# 13_Periphs.net
KiCad netlist of a schematic drawn in Altium Designer
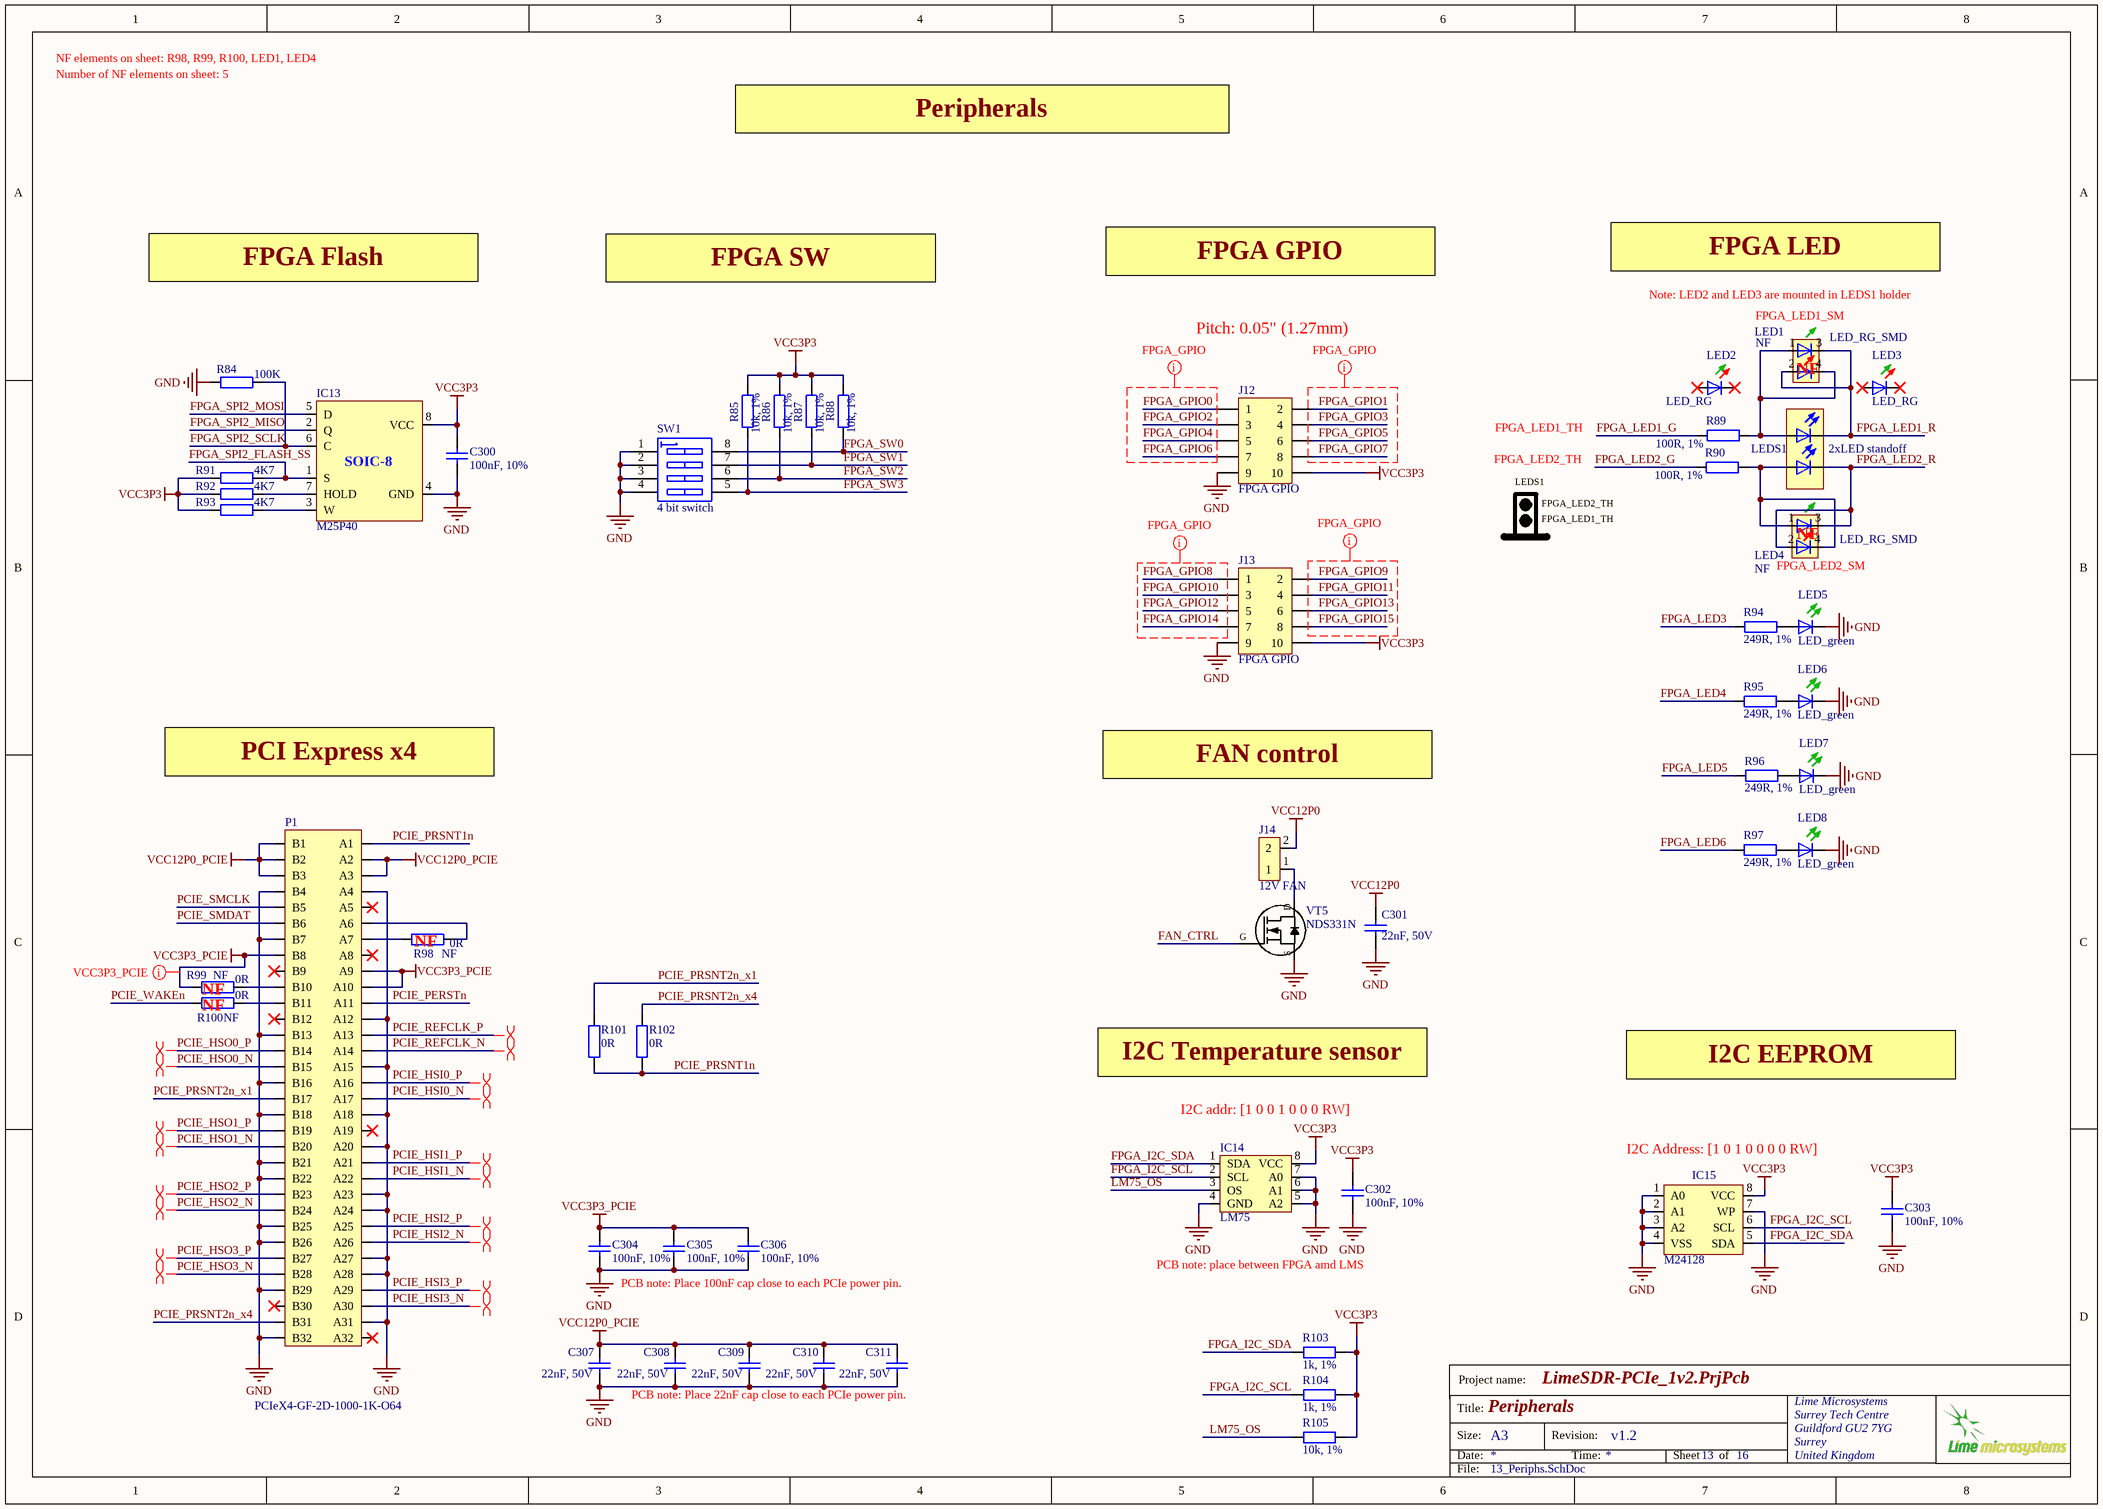
[diagram p0: 13_Periphs.SchDoc]

(export (version "E")
  (design (tool "Eeschema 10.0.6"))
  (components
    (comp (ref "C300")
      (value "100nF, 10%")
      (footprint "CAP0402")
      (fields
        (field (name "TOLERANCE") "10 %")
        (field (name "MANUFACTURER") "Murata Electronics")
        (field (name "MANUFACTURER PART NUMBER") "GRM155R71C104KA88D")
      )
      (libsource (lib "LimeFPGAboard_schLib") (part "Cap_0603"))
    )
    (comp (ref "C301")
      (value "22nF, 50V")
      (footprint "CAP0402")
      (fields (field (name "TOLERANCE") "±10%") (field (name "MANUFACTURER") "Kemet"))
      (libsource (lib "LimeMicroAltiumLib_schLib") (part "Cap_0402"))
    )
    (comp (ref "C302")
      (value "100nF, 10%")
      (footprint "CAP0402")
      (fields
        (field (name "TOLERANCE") "10 %")
        (field (name "MANUFACTURER") "Murata Electronics")
        (field (name "MANUFACTURER PART NUMBER") "GRM155R71C104KA88D")
      )
      (libsource (lib "LimeFPGAboard_schLib") (part "Cap_0603"))
    )
    (comp (ref "C303")
      (value "100nF, 10%")
      (footprint "CAP0402")
      (fields
        (field (name "TOLERANCE") "10 %")
        (field (name "MANUFACTURER") "Murata Electronics")
        (field (name "MANUFACTURER PART NUMBER") "GRM155R71C104KA88D")
      )
      (libsource (lib "LimeFPGAboard_schLib") (part "Cap_0603"))
    )
    (comp (ref "C304")
      (value "100nF, 10%")
      (footprint "CAP0402")
      (fields
        (field (name "TOLERANCE") "10 %")
        (field (name "MANUFACTURER") "Murata Electronics")
        (field (name "MANUFACTURER PART NUMBER") "GRM155R71C104KA88D")
      )
      (libsource (lib "LimeFPGAboard_schLib") (part "Cap_0603"))
    )
    (comp (ref "C305")
      (value "100nF, 10%")
      (footprint "CAP0402")
      (fields
        (field (name "TOLERANCE") "10 %")
        (field (name "MANUFACTURER") "Murata Electronics")
        (field (name "MANUFACTURER PART NUMBER") "GRM155R71C104KA88D")
      )
      (libsource (lib "LimeFPGAboard_schLib") (part "Cap_0603"))
    )
    (comp (ref "C306")
      (value "100nF, 10%")
      (footprint "CAP0402")
      (fields
        (field (name "TOLERANCE") "10 %")
        (field (name "MANUFACTURER") "Murata Electronics")
        (field (name "MANUFACTURER PART NUMBER") "GRM155R71C104KA88D")
      )
      (libsource (lib "LimeFPGAboard_schLib") (part "Cap_0603"))
    )
    (comp (ref "C307")
      (value "22nF, 50V")
      (footprint "CAP0402")
      (fields (field (name "TOLERANCE") "±10%") (field (name "MANUFACTURER") "Kemet"))
      (libsource (lib "LimeMicroAltiumLib_schLib") (part "Cap_0402"))
    )
    (comp (ref "C308")
      (value "22nF, 50V")
      (footprint "CAP0402")
      (fields (field (name "TOLERANCE") "±10%") (field (name "MANUFACTURER") "Kemet"))
      (libsource (lib "LimeMicroAltiumLib_schLib") (part "Cap_0402"))
    )
    (comp (ref "C309")
      (value "22nF, 50V")
      (footprint "CAP0402")
      (fields (field (name "TOLERANCE") "±10%") (field (name "MANUFACTURER") "Kemet"))
      (libsource (lib "LimeMicroAltiumLib_schLib") (part "Cap_0402"))
    )
    (comp (ref "C310")
      (value "22nF, 50V")
      (footprint "CAP0402")
      (fields (field (name "TOLERANCE") "±10%") (field (name "MANUFACTURER") "Kemet"))
      (libsource (lib "LimeMicroAltiumLib_schLib") (part "Cap_0402"))
    )
    (comp (ref "C311")
      (value "22nF, 50V")
      (footprint "CAP0402")
      (fields (field (name "TOLERANCE") "±10%") (field (name "MANUFACTURER") "Kemet"))
      (libsource (lib "LimeMicroAltiumLib_schLib") (part "Cap_0402"))
    )
    (comp (ref "IC13")
      (value "M25P40")
      (footprint "M25P40-VMN6TPB_SO8N")
      (fields (field (name "MANUFACTURER") "Micron Technology Inc"))
      (libsource (lib "LimeFPGAboard_schLib") (part "M25P40"))
    )
    (comp (ref "IC14")
      (value "LM75")
      (footprint "HWSON8_LM75")
      (fields
        (field (name "MANUFACTURER") "NXP Semiconductors")
        (field (name "MANUFACTURER PART NUMBER") "LM75BTP,147")
      )
      (libsource (lib "LimeMicroAltiumLib_schLib") (part "LM75"))
    )
    (comp (ref "IC15")
      (value "M24128")
      (footprint "24FC512")
      (fields (field (name "MANUFACTURER") "STMicroelectronics"))
      (libsource (lib "LimeMicroAltiumLib_schLib") (part "24FC64F"))
    )
    (comp (ref "J12")
      (value "FPGA GPIO")
      (footprint "SWD_10_pin")
      (description "Header, 5-Pin, Dual row")
      (fields (field (name "MANUFACTURER") "Harwin Inc"))
      (libsource (lib "LimeMicroAltiumLib_schLib") (part "Header 5X2_SWD"))
    )
    (comp (ref "J13")
      (value "FPGA GPIO")
      (footprint "SWD_10_pin")
      (description "Header, 5-Pin, Dual row")
      (fields (field (name "MANUFACTURER") "Harwin Inc"))
      (libsource (lib "LimeMicroAltiumLib_schLib") (part "Header 5X2_SWD"))
    )
    (comp (ref "J14")
      (value "12V FAN")
      (footprint "HDR_1x2")
      (fields (field (name "MANUFACTURER") "3M"))
      (libsource (lib "LimeFPGAboard_schLib") (part "Jumper"))
    )
    (comp (ref "LED1")
      (value "LED_RG_SMD")
      (footprint "LED-2x0603")
      (fields (field (name "MANUFACTURER") "Avago Technologies US Inc.") (field (name "ASSEMBLY INFO") "NF"))
      (libsource (lib "LimeMicroAltiumLib_schLib") (part "LED_green_red_SMD"))
    )
    (comp (ref "LED2")
      (value "LED_RG")
      (fields (field (name "MANUFACTURER") "Visual Communications Company - VCC"))
      (libsource (lib "LimeMicroAltiumLib_schLib") (part "LED_green_red"))
    )
    (comp (ref "LED3")
      (value "LED_RG")
      (fields (field (name "MANUFACTURER") "Visual Communications Company - VCC"))
      (libsource (lib "LimeMicroAltiumLib_schLib") (part "LED_green_red"))
    )
    (comp (ref "LED4")
      (value "LED_RG_SMD")
      (footprint "LED-2x0603")
      (fields (field (name "MANUFACTURER") "Avago Technologies US Inc.") (field (name "ASSEMBLY INFO") "NF"))
      (libsource (lib "LimeMicroAltiumLib_schLib") (part "LED_green_red_SMD"))
    )
    (comp (ref "LED5")
      (value "LED_green")
      (footprint "LED-0603-GREEN")
      (fields (field (name "MANUFACTURER") "Broadcom Limited"))
      (libsource (lib "LimeFPGAboard_schLib") (part "LED_green"))
    )
    (comp (ref "LED6")
      (value "LED_green")
      (footprint "LED-0603-GREEN")
      (fields (field (name "MANUFACTURER") "Broadcom Limited"))
      (libsource (lib "LimeFPGAboard_schLib") (part "LED_green"))
    )
    (comp (ref "LED7")
      (value "LED_green")
      (footprint "LED-0603-GREEN")
      (fields (field (name "MANUFACTURER") "Broadcom Limited"))
      (libsource (lib "LimeFPGAboard_schLib") (part "LED_green"))
    )
    (comp (ref "LED8")
      (value "LED_green")
      (footprint "LED-0603-GREEN")
      (fields (field (name "MANUFACTURER") "Broadcom Limited"))
      (libsource (lib "LimeFPGAboard_schLib") (part "LED_green"))
    )
    (comp (ref "LEDS1")
      (value "2xLED standoff")
      (footprint "LED_STANDOFF_H-201C")
      (fields (field (name "MANUFACTURER") "Bivar Inc."))
      (libsource (lib "LimeMicroAltiumLib_schLib") (part "LEDx2_STANDOFF"))
    )
    (comp (ref "P1")
      (value "PCIeX4-GF-2D-1000-1K-O64")
      (footprint "PCIeX4-GF-2D-1000-1K-O64")
      (libsource (lib "LimeMicroAltiumLib_schLib") (part "PCIeX4-GF-2D-1000-1K-O64"))
    )
    (comp (ref "R84")
      (value "100K")
      (footprint "RES0402")
      (fields
        (field (name "TOLERANCE") "±5%")
        (field (name "MANUFACTURER") "Panasonic Electronic Components")
      )
      (libsource (lib "LimeFPGAboard_schLib") (part "Res_0402"))
    )
    (comp (ref "R85")
      (value "10k, 1%")
      (footprint "RES0402")
      (fields (field (name "MANUFACTURER") "Yageo") (field (name "TOLERANCE") "±1%"))
      (libsource (lib "LimeMicroAltiumLib_schLib") (part "Res_0402"))
    )
    (comp (ref "R86")
      (value "10k, 1%")
      (footprint "RES0402")
      (fields (field (name "MANUFACTURER") "Yageo") (field (name "TOLERANCE") "±1%"))
      (libsource (lib "LimeMicroAltiumLib_schLib") (part "Res_0402"))
    )
    (comp (ref "R87")
      (value "10k, 1%")
      (footprint "RES0402")
      (fields (field (name "MANUFACTURER") "Yageo") (field (name "TOLERANCE") "±1%"))
      (libsource (lib "LimeMicroAltiumLib_schLib") (part "Res_0402"))
    )
    (comp (ref "R88")
      (value "10k, 1%")
      (footprint "RES0402")
      (fields (field (name "MANUFACTURER") "Yageo") (field (name "TOLERANCE") "±1%"))
      (libsource (lib "LimeMicroAltiumLib_schLib") (part "Res_0402"))
    )
    (comp (ref "R89")
      (value "100R, 1%")
      (footprint "RES0402")
      (fields (field (name "TOLERANCE") "±1%") (field (name "MANUFACTURER") "Stackpole Electronics Inc."))
      (libsource (lib "LimeMicroAltiumLib_schLib") (part "Res_0402"))
    )
    (comp (ref "R90")
      (value "100R, 1%")
      (footprint "RES0402")
      (fields (field (name "TOLERANCE") "±1%") (field (name "MANUFACTURER") "Stackpole Electronics Inc."))
      (libsource (lib "LimeMicroAltiumLib_schLib") (part "Res_0402"))
    )
    (comp (ref "R91")
      (value "4K7")
      (footprint "RES0402")
      (fields (field (name "TOLERANCE") "±5%") (field (name "MANUFACTURER") "Stackpole Electronics Inc."))
      (libsource (lib "LimeFPGAboard_schLib") (part "Res_0402"))
    )
    (comp (ref "R92")
      (value "4K7")
      (footprint "RES0402")
      (fields (field (name "TOLERANCE") "±5%") (field (name "MANUFACTURER") "Stackpole Electronics Inc."))
      (libsource (lib "LimeFPGAboard_schLib") (part "Res_0402"))
    )
    (comp (ref "R93")
      (value "4K7")
      (footprint "RES0402")
      (fields (field (name "TOLERANCE") "±5%") (field (name "MANUFACTURER") "Stackpole Electronics Inc."))
      (libsource (lib "LimeFPGAboard_schLib") (part "Res_0402"))
    )
    (comp (ref "R94")
      (value "249R, 1%")
      (footprint "RES0402")
      (fields (field (name "MANUFACTURER") "Stackpole Electronics Inc") (field (name "TOLERANCE") "±1%"))
      (libsource (lib "LimeMicroAltiumLib_schLib") (part "Res_0402"))
    )
    (comp (ref "R95")
      (value "249R, 1%")
      (footprint "RES0402")
      (fields (field (name "MANUFACTURER") "Stackpole Electronics Inc") (field (name "TOLERANCE") "±1%"))
      (libsource (lib "LimeMicroAltiumLib_schLib") (part "Res_0402"))
    )
    (comp (ref "R96")
      (value "249R, 1%")
      (footprint "RES0402")
      (fields (field (name "MANUFACTURER") "Stackpole Electronics Inc") (field (name "TOLERANCE") "±1%"))
      (libsource (lib "LimeMicroAltiumLib_schLib") (part "Res_0402"))
    )
    (comp (ref "R97")
      (value "249R, 1%")
      (footprint "RES0402")
      (fields (field (name "MANUFACTURER") "Stackpole Electronics Inc") (field (name "TOLERANCE") "±1%"))
      (libsource (lib "LimeMicroAltiumLib_schLib") (part "Res_0402"))
    )
    (comp (ref "R98")
      (value "0R")
      (footprint "RES0402")
      (fields (field (name "MANUFACTURER") "Yageo") (field (name "ASSEMBLY INFO") "NF"))
      (libsource (lib "LimeFPGAboard_schLib") (part "Res_0402"))
    )
    (comp (ref "R99")
      (value "0R")
      (footprint "RES0402")
      (fields (field (name "MANUFACTURER") "Yageo") (field (name "ASSEMBLY INFO") "NF"))
      (libsource (lib "LimeFPGAboard_schLib") (part "Res_0402"))
    )
    (comp (ref "R100")
      (value "0R")
      (footprint "RES0402")
      (fields (field (name "MANUFACTURER") "Yageo") (field (name "ASSEMBLY INFO") "NF"))
      (libsource (lib "LimeFPGAboard_schLib") (part "Res_0402"))
    )
    (comp (ref "R101")
      (value "0R")
      (footprint "RES0402")
      (fields (field (name "MANUFACTURER") "Yageo"))
      (libsource (lib "LimeFPGAboard_schLib") (part "Res_0402"))
    )
    (comp (ref "R102")
      (value "0R")
      (footprint "RES0402")
      (fields (field (name "MANUFACTURER") "Yageo"))
      (libsource (lib "LimeFPGAboard_schLib") (part "Res_0402"))
    )
    (comp (ref "R103")
      (value "1k, 1%")
      (footprint "RES0402")
      (fields (field (name "MANUFACTURER") "Stackpole Electronics Inc") (field (name "TOLERANCE") "±1%"))
      (libsource (lib "LimeMicroAltiumLib_schLib") (part "Res_0402"))
    )
    (comp (ref "R104")
      (value "1k, 1%")
      (footprint "RES0402")
      (fields (field (name "MANUFACTURER") "Stackpole Electronics Inc") (field (name "TOLERANCE") "±1%"))
      (libsource (lib "LimeMicroAltiumLib_schLib") (part "Res_0402"))
    )
    (comp (ref "R105")
      (value "10k, 1%")
      (footprint "RES0402")
      (fields (field (name "MANUFACTURER") "Yageo") (field (name "TOLERANCE") "±1%"))
      (libsource (lib "LimeMicroAltiumLib_schLib") (part "Res_0402"))
    )
    (comp (ref "SW1")
      (value "4 bit switch")
      (footprint "SW_4WAY_SMD_1P27")
      (fields (field (name "MANUFACTURER") "Omron Electronics Inc-EMC Div"))
      (libsource (lib "LimeMicroAltiumLib_schLib") (part "SW_SM_4bit"))
    )
    (comp (ref "VT5")
      (value "NDS331N")
      (footprint "SOT23-3")
      (fields (field (name "MANUFACTURER") "FAIRCHILD SEMICONDUCTOR"))
      (libsource (lib "LimeFPGAboard_schLib") (part "NDS331N"))
    )
  )
  (nets
    (net (code "1") (name "/FAN_CTRL") (class "Default")
      (node (ref "VT5") (pin "G") (pinfunction "G_G") (pintype "passive"))
    )
    (net (code "2") (name "/FPGA_GPIO0") (class "Default")
      (node (ref "J12") (pin "1") (pinfunction "1_1") (pintype "passive"))
    )
    (net (code "3") (name "/FPGA_GPIO1") (class "Default")
      (node (ref "J12") (pin "2") (pinfunction "2_2") (pintype "passive"))
    )
    (net (code "4") (name "/FPGA_GPIO2") (class "Default")
      (node (ref "J12") (pin "3") (pinfunction "3_3") (pintype "passive"))
    )
    (net (code "5") (name "/FPGA_GPIO3") (class "Default")
      (node (ref "J12") (pin "4") (pinfunction "4_4") (pintype "passive"))
    )
    (net (code "6") (name "/FPGA_GPIO4") (class "Default")
      (node (ref "J12") (pin "5") (pinfunction "5_5") (pintype "passive"))
    )
    (net (code "7") (name "/FPGA_GPIO5") (class "Default")
      (node (ref "J12") (pin "6") (pinfunction "6_6") (pintype "passive"))
    )
    (net (code "8") (name "/FPGA_GPIO6") (class "Default")
      (node (ref "J12") (pin "7") (pinfunction "7_7") (pintype "passive"))
    )
    (net (code "9") (name "/FPGA_GPIO7") (class "Default")
      (node (ref "J12") (pin "8") (pinfunction "8_8") (pintype "passive"))
    )
    (net (code "10") (name "/FPGA_GPIO8") (class "Default")
      (node (ref "J13") (pin "1") (pinfunction "1_1") (pintype "passive"))
    )
    (net (code "11") (name "/FPGA_GPIO9") (class "Default")
      (node (ref "J13") (pin "2") (pinfunction "2_2") (pintype "passive"))
    )
    (net (code "12") (name "/FPGA_GPIO10") (class "Default")
      (node (ref "J13") (pin "3") (pinfunction "3_3") (pintype "passive"))
    )
    (net (code "13") (name "/FPGA_GPIO11") (class "Default")
      (node (ref "J13") (pin "4") (pinfunction "4_4") (pintype "passive"))
    )
    (net (code "14") (name "/FPGA_GPIO12") (class "Default")
      (node (ref "J13") (pin "5") (pinfunction "5_5") (pintype "passive"))
    )
    (net (code "15") (name "/FPGA_GPIO13") (class "Default")
      (node (ref "J13") (pin "6") (pinfunction "6_6") (pintype "passive"))
    )
    (net (code "16") (name "/FPGA_GPIO14") (class "Default")
      (node (ref "J13") (pin "7") (pinfunction "7_7") (pintype "passive"))
    )
    (net (code "17") (name "/FPGA_GPIO15") (class "Default")
      (node (ref "J13") (pin "8") (pinfunction "8_8") (pintype "passive"))
    )
    (net (code "18") (name "/FPGA_I2C_SCL") (class "Default")
      (node (ref "IC14") (pin "2") (pinfunction "SCL_2") (pintype "passive"))
      (node (ref "IC15") (pin "6") (pinfunction "SCL_6") (pintype "passive"))
      (node (ref "R104") (pin "2") (pinfunction "2_2") (pintype "passive"))
    )
    (net (code "19") (name "/FPGA_I2C_SDA") (class "Default")
      (node (ref "IC14") (pin "1") (pinfunction "SDA_1") (pintype "passive"))
      (node (ref "IC15") (pin "5") (pinfunction "SDA_5") (pintype "passive"))
      (node (ref "R103") (pin "2") (pinfunction "2_2") (pintype "passive"))
    )
    (net (code "20") (name "/FPGA_LED1_G") (class "Default")
      (node (ref "R89") (pin "1") (pinfunction "1_1") (pintype "passive"))
    )
    (net (code "21") (name "/FPGA_LED1_R") (class "Default")
      (node (ref "LED1") (pin "2") (pinfunction "2_2") (pintype "power_in"))
      (node (ref "LED1") (pin "3") (pinfunction "3_3") (pintype "power_in"))
      (node (ref "LEDS1") (pin "K1") (pinfunction "C_K1") (pintype "power_in"))
    )
    (net (code "22") (name "/FPGA_LED2_G") (class "Default")
      (node (ref "R90") (pin "1") (pinfunction "1_1") (pintype "passive"))
    )
    (net (code "23") (name "/FPGA_LED2_R") (class "Default")
      (node (ref "LED4") (pin "2") (pinfunction "2_2") (pintype "power_in"))
      (node (ref "LED4") (pin "3") (pinfunction "3_3") (pintype "power_in"))
      (node (ref "LEDS1") (pin "K2") (pinfunction "C_K2") (pintype "power_in"))
    )
    (net (code "24") (name "/FPGA_LED3") (class "Default")
      (node (ref "R94") (pin "1") (pinfunction "1_1") (pintype "passive"))
    )
    (net (code "25") (name "/FPGA_LED4") (class "Default")
      (node (ref "R95") (pin "1") (pinfunction "1_1") (pintype "passive"))
    )
    (net (code "26") (name "/FPGA_LED5") (class "Default")
      (node (ref "R96") (pin "1") (pinfunction "1_1") (pintype "passive"))
    )
    (net (code "27") (name "/FPGA_LED6") (class "Default")
      (node (ref "R97") (pin "1") (pinfunction "1_1") (pintype "passive"))
    )
    (net (code "28") (name "/FPGA_SPI2_FLASH_SS") (class "Default")
      (node (ref "IC13") (pin "1") (pinfunction "S_1") (pintype "passive"))
      (node (ref "R91") (pin "2") (pinfunction "2_2") (pintype "passive"))
    )
    (net (code "29") (name "/FPGA_SPI2_MISO") (class "Default")
      (node (ref "IC13") (pin "2") (pinfunction "Q_2") (pintype "passive"))
    )
    (net (code "30") (name "/FPGA_SPI2_MOSI") (class "Default")
      (node (ref "IC13") (pin "5") (pinfunction "D_5") (pintype "passive"))
    )
    (net (code "31") (name "/FPGA_SPI2_SCLK") (class "Default")
      (node (ref "IC13") (pin "6") (pinfunction "C_6") (pintype "passive"))
      (node (ref "R84") (pin "2") (pinfunction "2_2") (pintype "passive"))
    )
    (net (code "32") (name "/FPGA_SW0") (class "Default")
      (node (ref "R88") (pin "2") (pinfunction "2_2") (pintype "passive"))
      (node (ref "SW1") (pin "8") (pinfunction "B1_8") (pintype "passive"))
    )
    (net (code "33") (name "/FPGA_SW1") (class "Default")
      (node (ref "R87") (pin "2") (pinfunction "2_2") (pintype "passive"))
      (node (ref "SW1") (pin "7") (pinfunction "B2_7") (pintype "passive"))
    )
    (net (code "34") (name "/FPGA_SW2") (class "Default")
      (node (ref "R86") (pin "2") (pinfunction "2_2") (pintype "passive"))
      (node (ref "SW1") (pin "6") (pinfunction "B3_6") (pintype "passive"))
    )
    (net (code "35") (name "/FPGA_SW3") (class "Default")
      (node (ref "R85") (pin "2") (pinfunction "2_2") (pintype "passive"))
      (node (ref "SW1") (pin "5") (pinfunction "B4_5") (pintype "passive"))
    )
    (net (code "36") (name "/LM75_OS") (class "Default")
      (node (ref "IC14") (pin "3") (pinfunction "OS_3") (pintype "passive"))
      (node (ref "R105") (pin "2") (pinfunction "2_2") (pintype "passive"))
    )
    (net (code "37") (name "/PCIE_HSI0_N") (class "Default")
      (node (ref "P1") (pin "A17") (pinfunction "A17_A17") (pintype "passive"))
    )
    (net (code "38") (name "/PCIE_HSI0_P") (class "Default")
      (node (ref "P1") (pin "A16") (pinfunction "A16_A16") (pintype "passive"))
    )
    (net (code "39") (name "/PCIE_HSI1_N") (class "Default")
      (node (ref "P1") (pin "A22") (pinfunction "A22_A22") (pintype "passive"))
    )
    (net (code "40") (name "/PCIE_HSI1_P") (class "Default")
      (node (ref "P1") (pin "A21") (pinfunction "A21_A21") (pintype "passive"))
    )
    (net (code "41") (name "/PCIE_HSI2_N") (class "Default")
      (node (ref "P1") (pin "A26") (pinfunction "A26_A26") (pintype "passive"))
    )
    (net (code "42") (name "/PCIE_HSI2_P") (class "Default")
      (node (ref "P1") (pin "A25") (pinfunction "A25_A25") (pintype "passive"))
    )
    (net (code "43") (name "/PCIE_HSI3_N") (class "Default")
      (node (ref "P1") (pin "A30") (pinfunction "A30_A30") (pintype "passive"))
    )
    (net (code "44") (name "/PCIE_HSI3_P") (class "Default")
      (node (ref "P1") (pin "A29") (pinfunction "A29_A29") (pintype "passive"))
    )
    (net (code "45") (name "/PCIE_HSO0_N") (class "Default")
      (node (ref "P1") (pin "B15") (pinfunction "B15_B15") (pintype "passive"))
    )
    (net (code "46") (name "/PCIE_HSO0_P") (class "Default")
      (node (ref "P1") (pin "B14") (pinfunction "B14_B14") (pintype "passive"))
    )
    (net (code "47") (name "/PCIE_HSO1_N") (class "Default")
      (node (ref "P1") (pin "B20") (pinfunction "B20_B20") (pintype "passive"))
    )
    (net (code "48") (name "/PCIE_HSO1_P") (class "Default")
      (node (ref "P1") (pin "B19") (pinfunction "B19_B19") (pintype "passive"))
    )
    (net (code "49") (name "/PCIE_HSO2_N") (class "Default")
      (node (ref "P1") (pin "B24") (pinfunction "B24_B24") (pintype "passive"))
    )
    (net (code "50") (name "/PCIE_HSO2_P") (class "Default")
      (node (ref "P1") (pin "B23") (pinfunction "B23_B23") (pintype "passive"))
    )
    (net (code "51") (name "/PCIE_HSO3_N") (class "Default")
      (node (ref "P1") (pin "B28") (pinfunction "B28_B28") (pintype "passive"))
    )
    (net (code "52") (name "/PCIE_HSO3_P") (class "Default")
      (node (ref "P1") (pin "B27") (pinfunction "B27_B27") (pintype "passive"))
    )
    (net (code "53") (name "/PCIE_PERSTn") (class "Default")
      (node (ref "P1") (pin "A11") (pinfunction "A11_A11") (pintype "passive"))
    )
    (net (code "54") (name "/PCIE_PRSNT1n") (class "Default")
      (node (ref "P1") (pin "A1") (pinfunction "A1_A1") (pintype "passive"))
      (node (ref "R101") (pin "1") (pinfunction "1_1") (pintype "passive"))
      (node (ref "R102") (pin "1") (pinfunction "1_1") (pintype "passive"))
    )
    (net (code "55") (name "/PCIE_PRSNT2n_x1") (class "Default")
      (node (ref "P1") (pin "B17") (pinfunction "B17_B17") (pintype "passive"))
      (node (ref "R101") (pin "2") (pinfunction "2_2") (pintype "passive"))
    )
    (net (code "56") (name "/PCIE_PRSNT2n_x4") (class "Default")
      (node (ref "P1") (pin "B31") (pinfunction "B31_B31") (pintype "passive"))
      (node (ref "R102") (pin "2") (pinfunction "2_2") (pintype "passive"))
    )
    (net (code "57") (name "/PCIE_REFCLK_N") (class "Default")
      (node (ref "P1") (pin "A14") (pinfunction "A14_A14") (pintype "passive"))
    )
    (net (code "58") (name "/PCIE_REFCLK_P") (class "Default")
      (node (ref "P1") (pin "A13") (pinfunction "A13_A13") (pintype "passive"))
    )
    (net (code "59") (name "/PCIE_SMCLK") (class "Default")
      (node (ref "P1") (pin "B5") (pinfunction "B5_B5") (pintype "passive"))
    )
    (net (code "60") (name "/PCIE_SMDAT") (class "Default")
      (node (ref "P1") (pin "B6") (pinfunction "B6_B6") (pintype "passive"))
    )
    (net (code "61") (name "/PCIE_WAKEn") (class "Default")
      (node (ref "R100") (pin "1") (pinfunction "1_1") (pintype "passive"))
    )
    (net (code "62") (name "GND") (class "Default")
      (node (ref "C300") (pin "2") (pinfunction "2_2") (pintype "passive"))
      (node (ref "C301") (pin "2") (pinfunction "2_2") (pintype "passive"))
      (node (ref "C302") (pin "2") (pinfunction "2_2") (pintype "passive"))
      (node (ref "C303") (pin "2") (pinfunction "2_2") (pintype "passive"))
      (node (ref "C304") (pin "2") (pinfunction "2_2") (pintype "passive"))
      (node (ref "C305") (pin "2") (pinfunction "2_2") (pintype "passive"))
      (node (ref "C306") (pin "2") (pinfunction "2_2") (pintype "passive"))
      (node (ref "C307") (pin "2") (pinfunction "2_2") (pintype "passive"))
      (node (ref "C308") (pin "2") (pinfunction "2_2") (pintype "passive"))
      (node (ref "C309") (pin "2") (pinfunction "2_2") (pintype "passive"))
      (node (ref "C310") (pin "2") (pinfunction "2_2") (pintype "passive"))
      (node (ref "C311") (pin "2") (pinfunction "2_2") (pintype "passive"))
      (node (ref "IC13") (pin "4") (pinfunction "GND_4") (pintype "passive"))
      (node (ref "IC14") (pin "4") (pinfunction "GND_4") (pintype "passive"))
      (node (ref "IC14") (pin "5") (pinfunction "A2_5") (pintype "passive"))
      (node (ref "IC14") (pin "6") (pinfunction "A1_6") (pintype "passive"))
      (node (ref "IC14") (pin "7") (pinfunction "A0_7") (pintype "passive"))
      (node (ref "IC15") (pin "1") (pinfunction "A0_1") (pintype "passive"))
      (node (ref "IC15") (pin "2") (pinfunction "A1_2") (pintype "passive"))
      (node (ref "IC15") (pin "3") (pinfunction "A2_3") (pintype "passive"))
      (node (ref "IC15") (pin "4") (pinfunction "VSS_4") (pintype "passive"))
      (node (ref "IC15") (pin "7") (pinfunction "WP_7") (pintype "passive"))
      (node (ref "J12") (pin "9") (pinfunction "9_9") (pintype "passive"))
      (node (ref "J13") (pin "9") (pinfunction "9_9") (pintype "passive"))
      (node (ref "LED5") (pin "K") (pinfunction "C_K") (pintype "power_in"))
      (node (ref "LED6") (pin "K") (pinfunction "C_K") (pintype "power_in"))
      (node (ref "LED7") (pin "K") (pinfunction "C_K") (pintype "power_in"))
      (node (ref "LED8") (pin "K") (pinfunction "C_K") (pintype "power_in"))
      (node (ref "P1") (pin "A12") (pinfunction "A12_A12") (pintype "passive"))
      (node (ref "P1") (pin "A15") (pinfunction "A15_A15") (pintype "passive"))
      (node (ref "P1") (pin "A18") (pinfunction "A18_A18") (pintype "passive"))
      (node (ref "P1") (pin "A20") (pinfunction "A20_A20") (pintype "passive"))
      (node (ref "P1") (pin "A23") (pinfunction "A23_A23") (pintype "passive"))
      (node (ref "P1") (pin "A24") (pinfunction "A24_A24") (pintype "passive"))
      (node (ref "P1") (pin "A27") (pinfunction "A27_A27") (pintype "passive"))
      (node (ref "P1") (pin "A28") (pinfunction "A28_A28") (pintype "passive"))
      (node (ref "P1") (pin "A31") (pinfunction "A31_A31") (pintype "passive"))
      (node (ref "P1") (pin "A4") (pinfunction "A4_A4") (pintype "passive"))
      (node (ref "P1") (pin "B13") (pinfunction "B13_B13") (pintype "passive"))
      (node (ref "P1") (pin "B16") (pinfunction "B16_B16") (pintype "passive"))
      (node (ref "P1") (pin "B18") (pinfunction "B18_B18") (pintype "passive"))
      (node (ref "P1") (pin "B21") (pinfunction "B21_B21") (pintype "passive"))
      (node (ref "P1") (pin "B22") (pinfunction "B22_B22") (pintype "passive"))
      (node (ref "P1") (pin "B25") (pinfunction "B25_B25") (pintype "passive"))
      (node (ref "P1") (pin "B26") (pinfunction "B26_B26") (pintype "passive"))
      (node (ref "P1") (pin "B29") (pinfunction "B29_B29") (pintype "passive"))
      (node (ref "P1") (pin "B32") (pinfunction "B32_B32") (pintype "passive"))
      (node (ref "P1") (pin "B4") (pinfunction "B4_B4") (pintype "passive"))
      (node (ref "P1") (pin "B7") (pinfunction "B7_B7") (pintype "passive"))
      (node (ref "R84") (pin "1") (pinfunction "1_1") (pintype "passive"))
      (node (ref "SW1") (pin "1") (pinfunction "A1_1") (pintype "passive"))
      (node (ref "SW1") (pin "2") (pinfunction "A2_2") (pintype "passive"))
      (node (ref "SW1") (pin "3") (pinfunction "A3_3") (pintype "passive"))
      (node (ref "SW1") (pin "4") (pinfunction "A4_4") (pintype "passive"))
      (node (ref "VT5") (pin "S") (pinfunction "S_S") (pintype "passive"))
    )
    (net (code "63") (name "Net-(IC13-HOLD)") (class "Default")
      (node (ref "IC13") (pin "7") (pinfunction "HOLD_7") (pintype "passive"))
      (node (ref "R92") (pin "2") (pinfunction "2_2") (pintype "passive"))
    )
    (net (code "64") (name "Net-(IC13-W)") (class "Default")
      (node (ref "IC13") (pin "3") (pinfunction "W_3") (pintype "passive"))
      (node (ref "R93") (pin "2") (pinfunction "2_2") (pintype "passive"))
    )
    (net (code "65") (name "Net-(J14-Pad1)") (class "Default")
      (node (ref "J14") (pin "1") (pinfunction "1_1") (pintype "passive"))
      (node (ref "VT5") (pin "D") (pinfunction "D_D") (pintype "passive"))
    )
    (net (code "66") (name "Net-(LED1-Pad1)") (class "Default")
      (node (ref "LED1") (pin "1") (pinfunction "1_1") (pintype "power_in"))
      (node (ref "LED1") (pin "4") (pinfunction "4_4") (pintype "power_in"))
      (node (ref "LEDS1") (pin "A1") (pinfunction "A_A1") (pintype "power_in"))
      (node (ref "R89") (pin "2") (pinfunction "2_2") (pintype "passive"))
    )
    (net (code "67") (name "Net-(LED4-Pad1)") (class "Default")
      (node (ref "LED4") (pin "1") (pinfunction "1_1") (pintype "power_in"))
      (node (ref "LED4") (pin "4") (pinfunction "4_4") (pintype "power_in"))
      (node (ref "LEDS1") (pin "A2") (pinfunction "A_A2") (pintype "power_in"))
      (node (ref "R90") (pin "2") (pinfunction "2_2") (pintype "passive"))
    )
    (net (code "68") (name "Net-(LED5-PadA)") (class "Default")
      (node (ref "LED5") (pin "A") (pinfunction "A_A") (pintype "power_in"))
      (node (ref "R94") (pin "2") (pinfunction "2_2") (pintype "passive"))
    )
    (net (code "69") (name "Net-(LED6-PadA)") (class "Default")
      (node (ref "LED6") (pin "A") (pinfunction "A_A") (pintype "power_in"))
      (node (ref "R95") (pin "2") (pinfunction "2_2") (pintype "passive"))
    )
    (net (code "70") (name "Net-(LED7-PadA)") (class "Default")
      (node (ref "LED7") (pin "A") (pinfunction "A_A") (pintype "power_in"))
      (node (ref "R96") (pin "2") (pinfunction "2_2") (pintype "passive"))
    )
    (net (code "71") (name "Net-(LED8-PadA)") (class "Default")
      (node (ref "LED8") (pin "A") (pinfunction "A_A") (pintype "power_in"))
      (node (ref "R97") (pin "2") (pinfunction "2_2") (pintype "passive"))
    )
    (net (code "72") (name "Net-(P1-PadA6)") (class "Default")
      (node (ref "P1") (pin "A6") (pinfunction "A6_A6") (pintype "passive"))
      (node (ref "R98") (pin "2") (pinfunction "2_2") (pintype "passive"))
    )
    (net (code "73") (name "Net-(P1-PadA7)") (class "Default")
      (node (ref "P1") (pin "A7") (pinfunction "A7_A7") (pintype "passive"))
      (node (ref "R98") (pin "1") (pinfunction "1_1") (pintype "passive"))
    )
    (net (code "74") (name "Net-(P1-PadB10)") (class "Default")
      (node (ref "P1") (pin "B10") (pinfunction "B10_B10") (pintype "passive"))
      (node (ref "R99") (pin "2") (pinfunction "2_2") (pintype "passive"))
    )
    (net (code "75") (name "Net-(P1-PadB11)") (class "Default")
      (node (ref "P1") (pin "B11") (pinfunction "B11_B11") (pintype "passive"))
      (node (ref "R100") (pin "2") (pinfunction "2_2") (pintype "passive"))
    )
    (net (code "76") (name "VCC3P3") (class "Default")
      (node (ref "C300") (pin "1") (pinfunction "1_1") (pintype "passive"))
      (node (ref "C302") (pin "1") (pinfunction "1_1") (pintype "passive"))
      (node (ref "C303") (pin "1") (pinfunction "1_1") (pintype "passive"))
      (node (ref "IC13") (pin "8") (pinfunction "VCC_8") (pintype "passive"))
      (node (ref "IC14") (pin "8") (pinfunction "VCC_8") (pintype "passive"))
      (node (ref "IC15") (pin "8") (pinfunction "VCC_8") (pintype "passive"))
      (node (ref "J12") (pin "10") (pinfunction "10_10") (pintype "passive"))
      (node (ref "J13") (pin "10") (pinfunction "10_10") (pintype "passive"))
      (node (ref "R103") (pin "1") (pinfunction "1_1") (pintype "passive"))
      (node (ref "R104") (pin "1") (pinfunction "1_1") (pintype "passive"))
      (node (ref "R105") (pin "1") (pinfunction "1_1") (pintype "passive"))
      (node (ref "R85") (pin "1") (pinfunction "1_1") (pintype "passive"))
      (node (ref "R86") (pin "1") (pinfunction "1_1") (pintype "passive"))
      (node (ref "R87") (pin "1") (pinfunction "1_1") (pintype "passive"))
      (node (ref "R88") (pin "1") (pinfunction "1_1") (pintype "passive"))
      (node (ref "R91") (pin "1") (pinfunction "1_1") (pintype "passive"))
      (node (ref "R92") (pin "1") (pinfunction "1_1") (pintype "passive"))
      (node (ref "R93") (pin "1") (pinfunction "1_1") (pintype "passive"))
    )
    (net (code "77") (name "VCC3P3_PCIE") (class "Default")
      (node (ref "C304") (pin "1") (pinfunction "1_1") (pintype "passive"))
      (node (ref "C305") (pin "1") (pinfunction "1_1") (pintype "passive"))
      (node (ref "C306") (pin "1") (pinfunction "1_1") (pintype "passive"))
      (node (ref "P1") (pin "A10") (pinfunction "A10_A10") (pintype "passive"))
      (node (ref "P1") (pin "A9") (pinfunction "A9_A9") (pintype "passive"))
      (node (ref "P1") (pin "B8") (pinfunction "B8_B8") (pintype "passive"))
      (node (ref "R99") (pin "1") (pinfunction "1_1") (pintype "passive"))
    )
    (net (code "78") (name "VCC12P0") (class "Default")
      (node (ref "C301") (pin "1") (pinfunction "1_1") (pintype "passive"))
      (node (ref "J14") (pin "2") (pinfunction "2_2") (pintype "passive"))
    )
    (net (code "79") (name "VCC12P0_PCIE") (class "Default")
      (node (ref "C307") (pin "1") (pinfunction "1_1") (pintype "passive"))
      (node (ref "C308") (pin "1") (pinfunction "1_1") (pintype "passive"))
      (node (ref "C309") (pin "1") (pinfunction "1_1") (pintype "passive"))
      (node (ref "C310") (pin "1") (pinfunction "1_1") (pintype "passive"))
      (node (ref "C311") (pin "1") (pinfunction "1_1") (pintype "passive"))
      (node (ref "P1") (pin "A2") (pinfunction "A2_A2") (pintype "passive"))
      (node (ref "P1") (pin "A3") (pinfunction "A3_A3") (pintype "passive"))
      (node (ref "P1") (pin "B1") (pinfunction "B1_B1") (pintype "passive"))
      (node (ref "P1") (pin "B2") (pinfunction "B2_B2") (pintype "passive"))
      (node (ref "P1") (pin "B3") (pinfunction "B3_B3") (pintype "passive"))
    )
    (net (code "80") (name "unconnected-(LED2-C-PadK)") (class "Default")
      (node (ref "LED2") (pin "K") (pinfunction "C_K") (pintype "power_in+no_connect"))
    )
    (net (code "81") (name "unconnected-(LED2-PadA)") (class "Default")
      (node (ref "LED2") (pin "A") (pinfunction "A_A") (pintype "power_in+no_connect"))
    )
    (net (code "82") (name "unconnected-(LED3-C-PadK)") (class "Default")
      (node (ref "LED3") (pin "K") (pinfunction "C_K") (pintype "power_in+no_connect"))
    )
    (net (code "83") (name "unconnected-(LED3-PadA)") (class "Default")
      (node (ref "LED3") (pin "A") (pinfunction "A_A") (pintype "power_in+no_connect"))
    )
    (net (code "84") (name "unconnected-(P1-PadA5)") (class "Default")
      (node (ref "P1") (pin "A5") (pinfunction "A5_A5") (pintype "passive+no_connect"))
    )
    (net (code "85") (name "unconnected-(P1-PadA8)") (class "Default")
      (node (ref "P1") (pin "A8") (pinfunction "A8_A8") (pintype "passive+no_connect"))
    )
    (net (code "86") (name "unconnected-(P1-PadA19)") (class "Default")
      (node (ref "P1") (pin "A19") (pinfunction "A19_A19") (pintype "passive+no_connect"))
    )
    (net (code "87") (name "unconnected-(P1-PadA32)") (class "Default")
      (node (ref "P1") (pin "A32") (pinfunction "A32_A32") (pintype "passive+no_connect"))
    )
    (net (code "88") (name "unconnected-(P1-PadB9)") (class "Default")
      (node (ref "P1") (pin "B9") (pinfunction "B9_B9") (pintype "passive+no_connect"))
    )
    (net (code "89") (name "unconnected-(P1-PadB12)") (class "Default")
      (node (ref "P1") (pin "B12") (pinfunction "B12_B12") (pintype "passive+no_connect"))
    )
    (net (code "90") (name "unconnected-(P1-PadB30)") (class "Default")
      (node (ref "P1") (pin "B30") (pinfunction "B30_B30") (pintype "passive+no_connect"))
    )
  )
)
